# RelayDriver.net
KiCad netlist of a schematic drawn in Altium Designer
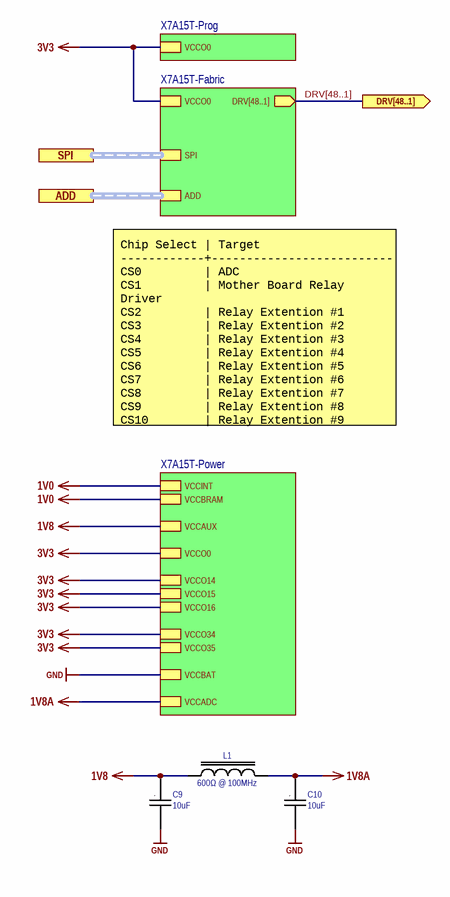
[diagram p0: RelayDriver.SchDoc]

(export (version "E")
  (design (tool "Eeschema 10.0.6"))
  (components
    (comp (ref "C9")
      (value "10uF")
      (footprint "C0805 Reflow")
      (description "CAP CER 10UF 10V X7R 0805")
      (fields
        (field (name "TOLERANCE") "±10%")
        (field (name "02. DISTRIBUTOR PART NUMBER") "1276-1764-6-ND")
        (field (name "13. CREATED DATE/NAME") "AUG2018/Hören")
      )
      (libsource (lib "chickenfood") (part "C"))
    )
    (comp (ref "C10")
      (value "10uF")
      (footprint "C0805 Reflow")
      (description "CAP CER 10UF 10V X7R 0805")
      (fields
        (field (name "TOLERANCE") "±10%")
        (field (name "02. DISTRIBUTOR PART NUMBER") "1276-1764-6-ND")
        (field (name "13. CREATED DATE/NAME") "AUG2018/Hören")
      )
      (libsource (lib "chickenfood") (part "C"))
    )
    (comp (ref "L1")
      (value "L")
      (footprint "FB0805")
      (description "FERRITE BEAD 600 OHM 0805 1LN")
      (fields
        (field (name "NOMINAL IMPEDANCE") "600Ω @ 100MHz")
        (field (name "02. DISTRIBUTOR PART NUMBER") "732-1620-6-ND")
        (field (name "07. MANUFACTURER  PART NUMBER") "742792040")
        (field (name "13. CREATED DATE/NAME") "AUG2018/Hören")
      )
      (libsource (lib "chickenfood") (part "FB"))
    )
  )
  (nets
    (net (code "55") (name "1V8") (class "Default")
      (node (ref "C9") (pin "1") (pinfunction "1_1") (pintype "passive"))
      (node (ref "L1") (pin "1") (pinfunction "1_1") (pintype "passive"))
    )
    (net (code "56") (name "1V8A") (class "Default")
      (node (ref "C10") (pin "1") (pinfunction "1_1") (pintype "passive"))
      (node (ref "L1") (pin "2") (pinfunction "2_2") (pintype "passive"))
    )
    (net (code "58") (name "GND") (class "Default")
      (node (ref "C10") (pin "2") (pinfunction "2_2") (pintype "passive"))
      (node (ref "C9") (pin "2") (pinfunction "2_2") (pintype "passive"))
    )
  )
)
